# leddriver.net
KiCad netlist of a schematic drawn in EAGLE
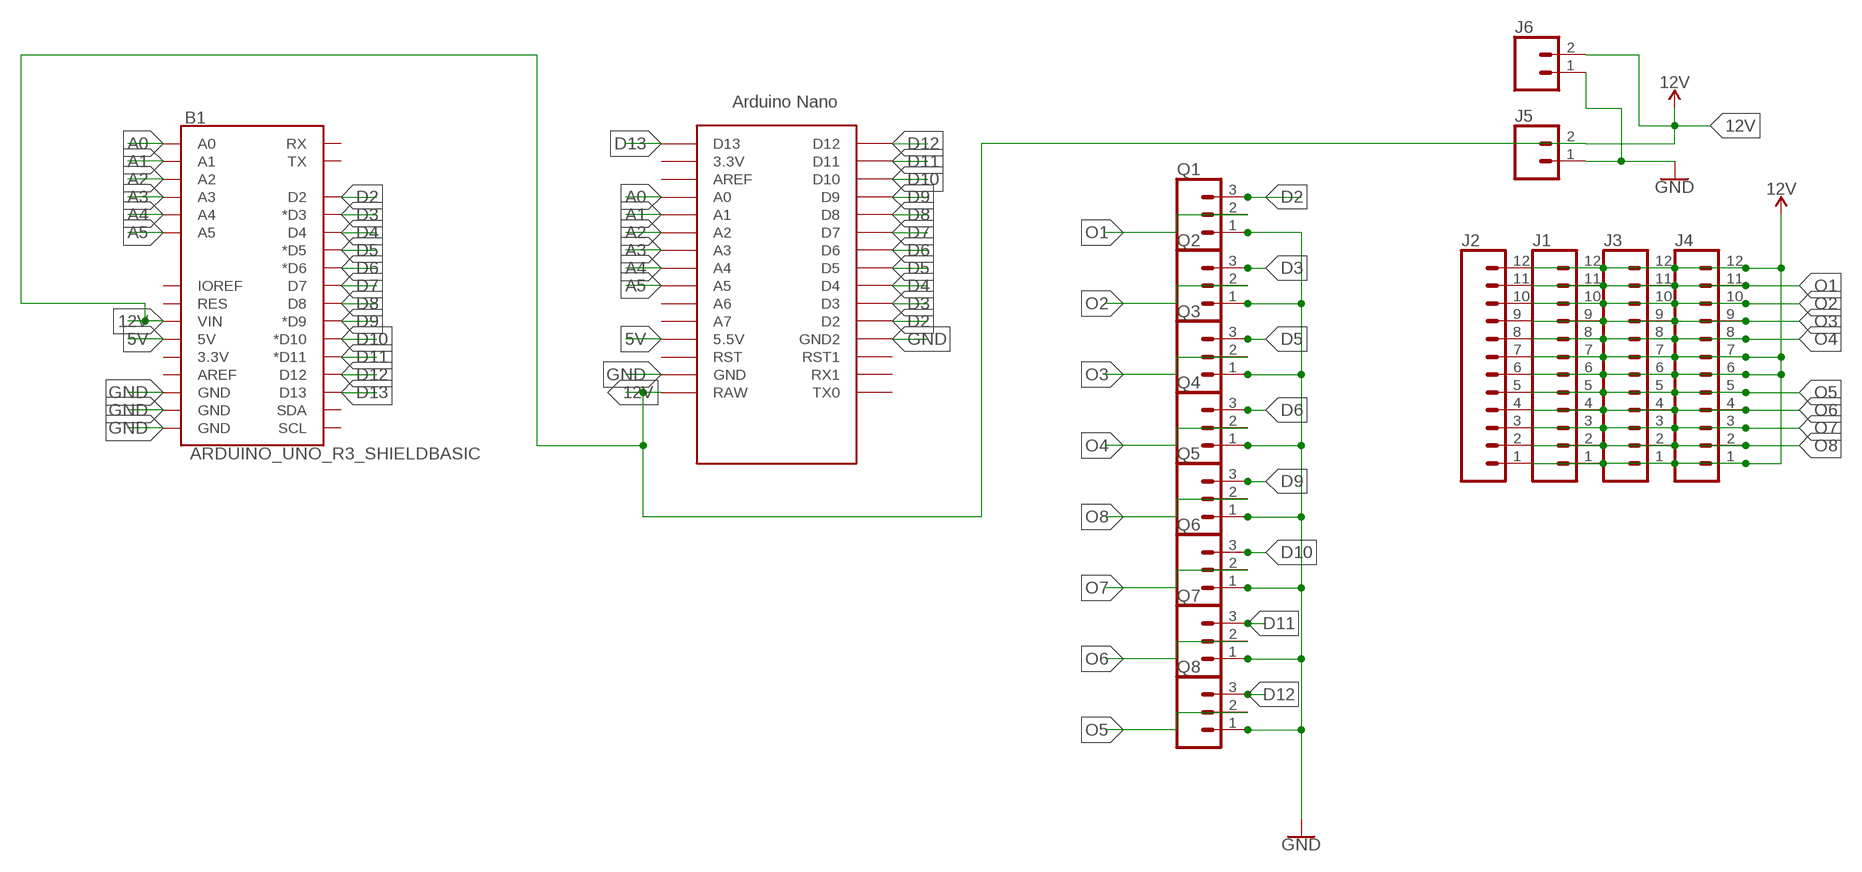
[diagram p0: schematic, sheet 1]

(export (version "E")
  (design (tool "Eeschema 10.0.6"))
  (components
    (comp (ref "B1")
      (value "ARDUINO_UNO_R3_SHIELDBASIC")
      (footprint "eagle-import:UNO_R3_SHIELD")
      (libsource (lib "eagle-import") (part "ARDUINO_UNO_R3_SHIELDBASIC"))
    )
    (comp (ref "J1")
      (value "CONN_12")
      (footprint "eagle-import:1X12")
      (libsource (lib "eagle-import") (part "CONN_12"))
    )
    (comp (ref "J2")
      (value "CONN_12")
      (footprint "eagle-import:1X12")
      (libsource (lib "eagle-import") (part "CONN_12"))
    )
    (comp (ref "J3")
      (value "CONN_12")
      (footprint "eagle-import:1X12")
      (libsource (lib "eagle-import") (part "CONN_12"))
    )
    (comp (ref "J4")
      (value "CONN_12")
      (footprint "eagle-import:1X12")
      (libsource (lib "eagle-import") (part "CONN_12"))
    )
    (comp (ref "J5")
      (value "CONN_02")
      (footprint "eagle-import:1X02")
      (libsource (lib "eagle-import") (part "CONN_02"))
    )
    (comp (ref "J6")
      (value "CONN_02")
      (footprint "eagle-import:1X02")
      (libsource (lib "eagle-import") (part "CONN_02"))
    )
    (comp (ref "Q1")
      (value "455-1750-1-ND")
      (footprint "eagle-import:1X03")
      (libsource (lib "eagle-import") (part "CONN_03"))
    )
    (comp (ref "Q2")
      (value "455-1750-1-ND")
      (footprint "eagle-import:1X03")
      (libsource (lib "eagle-import") (part "CONN_03"))
    )
    (comp (ref "Q3")
      (value "455-1750-1-ND")
      (footprint "eagle-import:1X03")
      (libsource (lib "eagle-import") (part "CONN_03"))
    )
    (comp (ref "Q4")
      (value "455-1750-1-ND")
      (footprint "eagle-import:1X03")
      (libsource (lib "eagle-import") (part "CONN_03"))
    )
    (comp (ref "Q5")
      (value "455-1750-1-ND")
      (footprint "eagle-import:1X03")
      (libsource (lib "eagle-import") (part "CONN_03"))
    )
    (comp (ref "Q6")
      (value "455-1750-1-ND")
      (footprint "eagle-import:1X03")
      (libsource (lib "eagle-import") (part "CONN_03"))
    )
    (comp (ref "Q7")
      (value "455-1750-1-ND")
      (footprint "eagle-import:1X03")
      (libsource (lib "eagle-import") (part "CONN_03"))
    )
    (comp (ref "Q8")
      (value "455-1750-1-ND")
      (footprint "eagle-import:1X03")
      (libsource (lib "eagle-import") (part "CONN_03"))
    )
    (comp (ref "U$1")
      (value "NANO")
      (footprint "eagle-import:NANO")
      (libsource (lib "eagle-import") (part "NANO"))
    )
  )
  (nets
    (net (code "1") (name "5V") (class "Default")
      (node (ref "B1") (pin "5V") (pinfunction "5V_5V") (pintype "bidirectional"))
      (node (ref "U$1") (pin "5V") (pinfunction "5.5V_5V") (pintype "bidirectional"))
    )
    (net (code "2") (name "12V") (class "Default")
      (node (ref "B1") (pin "VIN") (pinfunction "VIN_VIN") (pintype "bidirectional"))
      (node (ref "J1") (pin "1") (pinfunction "1_1") (pintype "passive"))
      (node (ref "J1") (pin "12") (pinfunction "12_12") (pintype "passive"))
      (node (ref "J1") (pin "6") (pinfunction "6_6") (pintype "passive"))
      (node (ref "J1") (pin "7") (pinfunction "7_7") (pintype "passive"))
      (node (ref "J2") (pin "1") (pinfunction "1_1") (pintype "passive"))
      (node (ref "J2") (pin "12") (pinfunction "12_12") (pintype "passive"))
      (node (ref "J2") (pin "6") (pinfunction "6_6") (pintype "passive"))
      (node (ref "J2") (pin "7") (pinfunction "7_7") (pintype "passive"))
      (node (ref "J3") (pin "1") (pinfunction "1_1") (pintype "passive"))
      (node (ref "J3") (pin "12") (pinfunction "12_12") (pintype "passive"))
      (node (ref "J3") (pin "6") (pinfunction "6_6") (pintype "passive"))
      (node (ref "J3") (pin "7") (pinfunction "7_7") (pintype "passive"))
      (node (ref "J4") (pin "1") (pinfunction "1_1") (pintype "passive"))
      (node (ref "J4") (pin "12") (pinfunction "12_12") (pintype "passive"))
      (node (ref "J4") (pin "6") (pinfunction "6_6") (pintype "passive"))
      (node (ref "J4") (pin "7") (pinfunction "7_7") (pintype "passive"))
      (node (ref "J5") (pin "2") (pinfunction "2_2") (pintype "passive"))
      (node (ref "J6") (pin "2") (pinfunction "2_2") (pintype "passive"))
      (node (ref "U$1") (pin "RAW") (pinfunction "RAW_RAW") (pintype "bidirectional"))
    )
    (net (code "3") (name "A0") (class "Default")
      (node (ref "B1") (pin "A0") (pinfunction "A0_A0") (pintype "bidirectional"))
      (node (ref "U$1") (pin "A0") (pinfunction "A0_A0") (pintype "bidirectional"))
    )
    (net (code "4") (name "A1") (class "Default")
      (node (ref "B1") (pin "A1") (pinfunction "A1_A1") (pintype "bidirectional"))
      (node (ref "U$1") (pin "A1") (pinfunction "A1_A1") (pintype "bidirectional"))
    )
    (net (code "5") (name "A2") (class "Default")
      (node (ref "B1") (pin "A2") (pinfunction "A2_A2") (pintype "bidirectional"))
      (node (ref "U$1") (pin "A2") (pinfunction "A2_A2") (pintype "bidirectional"))
    )
    (net (code "6") (name "A3") (class "Default")
      (node (ref "B1") (pin "A3") (pinfunction "A3_A3") (pintype "bidirectional"))
      (node (ref "U$1") (pin "A3") (pinfunction "A3_A3") (pintype "bidirectional"))
    )
    (net (code "7") (name "A4") (class "Default")
      (node (ref "B1") (pin "A4") (pinfunction "A4_A4") (pintype "bidirectional"))
      (node (ref "U$1") (pin "A4") (pinfunction "A4_A4") (pintype "bidirectional"))
    )
    (net (code "8") (name "A5") (class "Default")
      (node (ref "B1") (pin "A5") (pinfunction "A5_A5") (pintype "bidirectional"))
      (node (ref "U$1") (pin "A5") (pinfunction "A5_A5") (pintype "bidirectional"))
    )
    (net (code "9") (name "D2") (class "Default")
      (node (ref "B1") (pin "D2") (pinfunction "D2_D2") (pintype "bidirectional"))
      (node (ref "Q1") (pin "3") (pinfunction "3_3") (pintype "passive"))
      (node (ref "U$1") (pin "D2") (pinfunction "D2_D2") (pintype "bidirectional"))
    )
    (net (code "10") (name "D3") (class "Default")
      (node (ref "B1") (pin "D3") (pinfunction "*D3_D3") (pintype "bidirectional"))
      (node (ref "Q2") (pin "3") (pinfunction "3_3") (pintype "passive"))
      (node (ref "U$1") (pin "D3") (pinfunction "D3_D3") (pintype "bidirectional"))
    )
    (net (code "11") (name "D4") (class "Default")
      (node (ref "B1") (pin "D4") (pinfunction "D4_D4") (pintype "bidirectional"))
      (node (ref "U$1") (pin "D4") (pinfunction "D4_D4") (pintype "bidirectional"))
    )
    (net (code "12") (name "D5") (class "Default")
      (node (ref "B1") (pin "D5") (pinfunction "*D5_D5") (pintype "bidirectional"))
      (node (ref "Q3") (pin "3") (pinfunction "3_3") (pintype "passive"))
      (node (ref "U$1") (pin "D5") (pinfunction "D5_D5") (pintype "bidirectional"))
    )
    (net (code "13") (name "D6") (class "Default")
      (node (ref "B1") (pin "D6") (pinfunction "*D6_D6") (pintype "bidirectional"))
      (node (ref "Q4") (pin "3") (pinfunction "3_3") (pintype "passive"))
      (node (ref "U$1") (pin "D6") (pinfunction "D6_D6") (pintype "bidirectional"))
    )
    (net (code "14") (name "D7") (class "Default")
      (node (ref "B1") (pin "D7") (pinfunction "D7_D7") (pintype "bidirectional"))
      (node (ref "U$1") (pin "D7") (pinfunction "D7_D7") (pintype "bidirectional"))
    )
    (net (code "15") (name "D8") (class "Default")
      (node (ref "B1") (pin "D8") (pinfunction "D8_D8") (pintype "bidirectional"))
      (node (ref "U$1") (pin "D8") (pinfunction "D8_D8") (pintype "bidirectional"))
    )
    (net (code "16") (name "D9") (class "Default")
      (node (ref "B1") (pin "D9") (pinfunction "*D9_D9") (pintype "bidirectional"))
      (node (ref "Q5") (pin "3") (pinfunction "3_3") (pintype "passive"))
      (node (ref "U$1") (pin "D9") (pinfunction "D9_D9") (pintype "bidirectional"))
    )
    (net (code "17") (name "D10") (class "Default")
      (node (ref "B1") (pin "D10") (pinfunction "*D10_D10") (pintype "bidirectional"))
      (node (ref "Q6") (pin "3") (pinfunction "3_3") (pintype "passive"))
      (node (ref "U$1") (pin "D10") (pinfunction "D10_D10") (pintype "bidirectional"))
    )
    (net (code "18") (name "D11") (class "Default")
      (node (ref "B1") (pin "D11") (pinfunction "*D11_D11") (pintype "bidirectional"))
      (node (ref "Q7") (pin "3") (pinfunction "3_3") (pintype "passive"))
      (node (ref "U$1") (pin "D11") (pinfunction "D11_D11") (pintype "bidirectional"))
    )
    (net (code "19") (name "D12") (class "Default")
      (node (ref "B1") (pin "D12") (pinfunction "D12_D12") (pintype "bidirectional"))
      (node (ref "Q8") (pin "3") (pinfunction "3_3") (pintype "passive"))
      (node (ref "U$1") (pin "D12") (pinfunction "D12_D12") (pintype "bidirectional"))
    )
    (net (code "20") (name "D13") (class "Default")
      (node (ref "B1") (pin "D13") (pinfunction "D13_D13") (pintype "bidirectional"))
      (node (ref "U$1") (pin "D13") (pinfunction "D13_D13") (pintype "bidirectional"))
    )
    (net (code "21") (name "GND") (class "Default")
      (node (ref "B1") (pin "GND@0") (pinfunction "GND_GND@0") (pintype "bidirectional"))
      (node (ref "B1") (pin "GND@1") (pinfunction "GND_GND@1") (pintype "bidirectional"))
      (node (ref "B1") (pin "GND@2") (pinfunction "GND_GND@2") (pintype "bidirectional"))
      (node (ref "J5") (pin "1") (pinfunction "1_1") (pintype "passive"))
      (node (ref "J6") (pin "1") (pinfunction "1_1") (pintype "passive"))
      (node (ref "Q1") (pin "1") (pinfunction "1_1") (pintype "passive"))
      (node (ref "Q2") (pin "1") (pinfunction "1_1") (pintype "passive"))
      (node (ref "Q3") (pin "1") (pinfunction "1_1") (pintype "passive"))
      (node (ref "Q4") (pin "1") (pinfunction "1_1") (pintype "passive"))
      (node (ref "Q5") (pin "1") (pinfunction "1_1") (pintype "passive"))
      (node (ref "Q6") (pin "1") (pinfunction "1_1") (pintype "passive"))
      (node (ref "Q7") (pin "1") (pinfunction "1_1") (pintype "passive"))
      (node (ref "Q8") (pin "1") (pinfunction "1_1") (pintype "passive"))
      (node (ref "U$1") (pin "GND") (pinfunction "GND_GND") (pintype "bidirectional"))
      (node (ref "U$1") (pin "GND1") (pinfunction "GND2_GND1") (pintype "bidirectional"))
    )
    (net (code "22") (name "O1") (class "Default")
      (node (ref "J1") (pin "11") (pinfunction "11_11") (pintype "passive"))
      (node (ref "J2") (pin "11") (pinfunction "11_11") (pintype "passive"))
      (node (ref "J3") (pin "11") (pinfunction "11_11") (pintype "passive"))
      (node (ref "J4") (pin "11") (pinfunction "11_11") (pintype "passive"))
      (node (ref "Q1") (pin "2") (pinfunction "2_2") (pintype "passive"))
    )
    (net (code "23") (name "O2") (class "Default")
      (node (ref "J1") (pin "10") (pinfunction "10_10") (pintype "passive"))
      (node (ref "J2") (pin "10") (pinfunction "10_10") (pintype "passive"))
      (node (ref "J3") (pin "10") (pinfunction "10_10") (pintype "passive"))
      (node (ref "J4") (pin "10") (pinfunction "10_10") (pintype "passive"))
      (node (ref "Q2") (pin "2") (pinfunction "2_2") (pintype "passive"))
    )
    (net (code "24") (name "O3") (class "Default")
      (node (ref "J1") (pin "9") (pinfunction "9_9") (pintype "passive"))
      (node (ref "J2") (pin "9") (pinfunction "9_9") (pintype "passive"))
      (node (ref "J3") (pin "9") (pinfunction "9_9") (pintype "passive"))
      (node (ref "J4") (pin "9") (pinfunction "9_9") (pintype "passive"))
      (node (ref "Q3") (pin "2") (pinfunction "2_2") (pintype "passive"))
    )
    (net (code "25") (name "O4") (class "Default")
      (node (ref "J1") (pin "8") (pinfunction "8_8") (pintype "passive"))
      (node (ref "J2") (pin "8") (pinfunction "8_8") (pintype "passive"))
      (node (ref "J3") (pin "8") (pinfunction "8_8") (pintype "passive"))
      (node (ref "J4") (pin "8") (pinfunction "8_8") (pintype "passive"))
      (node (ref "Q4") (pin "2") (pinfunction "2_2") (pintype "passive"))
    )
    (net (code "26") (name "O5") (class "Default")
      (node (ref "J1") (pin "5") (pinfunction "5_5") (pintype "passive"))
      (node (ref "J2") (pin "5") (pinfunction "5_5") (pintype "passive"))
      (node (ref "J3") (pin "5") (pinfunction "5_5") (pintype "passive"))
      (node (ref "J4") (pin "5") (pinfunction "5_5") (pintype "passive"))
      (node (ref "Q8") (pin "2") (pinfunction "2_2") (pintype "passive"))
    )
    (net (code "27") (name "O6") (class "Default")
      (node (ref "J1") (pin "4") (pinfunction "4_4") (pintype "passive"))
      (node (ref "J2") (pin "4") (pinfunction "4_4") (pintype "passive"))
      (node (ref "J3") (pin "4") (pinfunction "4_4") (pintype "passive"))
      (node (ref "J4") (pin "4") (pinfunction "4_4") (pintype "passive"))
      (node (ref "Q7") (pin "2") (pinfunction "2_2") (pintype "passive"))
    )
    (net (code "28") (name "O7") (class "Default")
      (node (ref "J1") (pin "3") (pinfunction "3_3") (pintype "passive"))
      (node (ref "J2") (pin "3") (pinfunction "3_3") (pintype "passive"))
      (node (ref "J3") (pin "3") (pinfunction "3_3") (pintype "passive"))
      (node (ref "J4") (pin "3") (pinfunction "3_3") (pintype "passive"))
      (node (ref "Q6") (pin "2") (pinfunction "2_2") (pintype "passive"))
    )
    (net (code "29") (name "O8") (class "Default")
      (node (ref "J1") (pin "2") (pinfunction "2_2") (pintype "passive"))
      (node (ref "J2") (pin "2") (pinfunction "2_2") (pintype "passive"))
      (node (ref "J3") (pin "2") (pinfunction "2_2") (pintype "passive"))
      (node (ref "J4") (pin "2") (pinfunction "2_2") (pintype "passive"))
      (node (ref "Q5") (pin "2") (pinfunction "2_2") (pintype "passive"))
    )
    (net (code "30") (name "unconnected-(B1-Pad3.3V)") (class "Default")
      (node (ref "B1") (pin "3.3V") (pinfunction "3.3V_3.3V") (pintype "bidirectional"))
    )
    (net (code "31") (name "unconnected-(B1-PadAREF)") (class "Default")
      (node (ref "B1") (pin "AREF") (pinfunction "AREF_AREF") (pintype "bidirectional"))
    )
    (net (code "32") (name "unconnected-(B1-PadIOREF)") (class "Default")
      (node (ref "B1") (pin "IOREF") (pinfunction "IOREF_IOREF") (pintype "bidirectional"))
    )
    (net (code "33") (name "unconnected-(B1-PadRES)") (class "Default")
      (node (ref "B1") (pin "RES") (pinfunction "RES_RES") (pintype "bidirectional"))
    )
    (net (code "34") (name "unconnected-(B1-PadRX)") (class "Default")
      (node (ref "B1") (pin "RX") (pinfunction "RX_RX") (pintype "bidirectional"))
    )
    (net (code "35") (name "unconnected-(B1-PadSCL)") (class "Default")
      (node (ref "B1") (pin "SCL") (pinfunction "SCL_SCL") (pintype "bidirectional"))
    )
    (net (code "36") (name "unconnected-(B1-PadSDA)") (class "Default")
      (node (ref "B1") (pin "SDA") (pinfunction "SDA_SDA") (pintype "bidirectional"))
    )
    (net (code "37") (name "unconnected-(B1-PadTX)") (class "Default")
      (node (ref "B1") (pin "TX") (pinfunction "TX_TX") (pintype "bidirectional"))
    )
    (net (code "38") (name "unconnected-(U$1-Pad3.3V)") (class "Default")
      (node (ref "U$1") (pin "3.3V") (pinfunction "3.3V_3.3V") (pintype "bidirectional"))
    )
    (net (code "39") (name "unconnected-(U$1-PadA6)") (class "Default")
      (node (ref "U$1") (pin "A6") (pinfunction "A6_A6") (pintype "bidirectional"))
    )
    (net (code "40") (name "unconnected-(U$1-PadA7)") (class "Default")
      (node (ref "U$1") (pin "A7") (pinfunction "A7_A7") (pintype "bidirectional"))
    )
    (net (code "41") (name "unconnected-(U$1-PadAREF)") (class "Default")
      (node (ref "U$1") (pin "AREF") (pinfunction "AREF_AREF") (pintype "bidirectional"))
    )
    (net (code "42") (name "unconnected-(U$1-PadICSP1)") (class "Default")
      (node (ref "U$1") (pin "ICSP1") (pinfunction "ICSP1_ICSP1") (pintype "bidirectional"))
    )
    (net (code "43") (name "unconnected-(U$1-PadICSP2)") (class "Default")
      (node (ref "U$1") (pin "ICSP2") (pinfunction "ICSP2_ICSP2") (pintype "bidirectional"))
    )
    (net (code "44") (name "unconnected-(U$1-PadICSP3)") (class "Default")
      (node (ref "U$1") (pin "ICSP3") (pinfunction "ICSP3_ICSP3") (pintype "bidirectional"))
    )
    (net (code "45") (name "unconnected-(U$1-PadICSP4)") (class "Default")
      (node (ref "U$1") (pin "ICSP4") (pinfunction "ICSP4_ICSP4") (pintype "bidirectional"))
    )
    (net (code "46") (name "unconnected-(U$1-PadICSP5)") (class "Default")
      (node (ref "U$1") (pin "ICSP5") (pinfunction "ICSP5_ICSP5") (pintype "bidirectional"))
    )
    (net (code "47") (name "unconnected-(U$1-PadICSP6)") (class "Default")
      (node (ref "U$1") (pin "ICSP6") (pinfunction "ICSP6_ICSP6") (pintype "bidirectional"))
    )
    (net (code "48") (name "unconnected-(U$1-PadRST)") (class "Default")
      (node (ref "U$1") (pin "RST") (pinfunction "RST_RST") (pintype "bidirectional"))
    )
    (net (code "49") (name "unconnected-(U$1-PadRST1)") (class "Default")
      (node (ref "U$1") (pin "RST1") (pinfunction "RST1_RST1") (pintype "bidirectional"))
    )
    (net (code "50") (name "unconnected-(U$1-PadRX1)") (class "Default")
      (node (ref "U$1") (pin "RX1") (pinfunction "RX1_RX1") (pintype "bidirectional"))
    )
    (net (code "51") (name "unconnected-(U$1-PadTX0)") (class "Default")
      (node (ref "U$1") (pin "TX0") (pinfunction "TX0_TX0") (pintype "bidirectional"))
    )
  )
)
